# TheRealMainboardSCH.net
KiCad netlist of a schematic drawn in Altium Designer
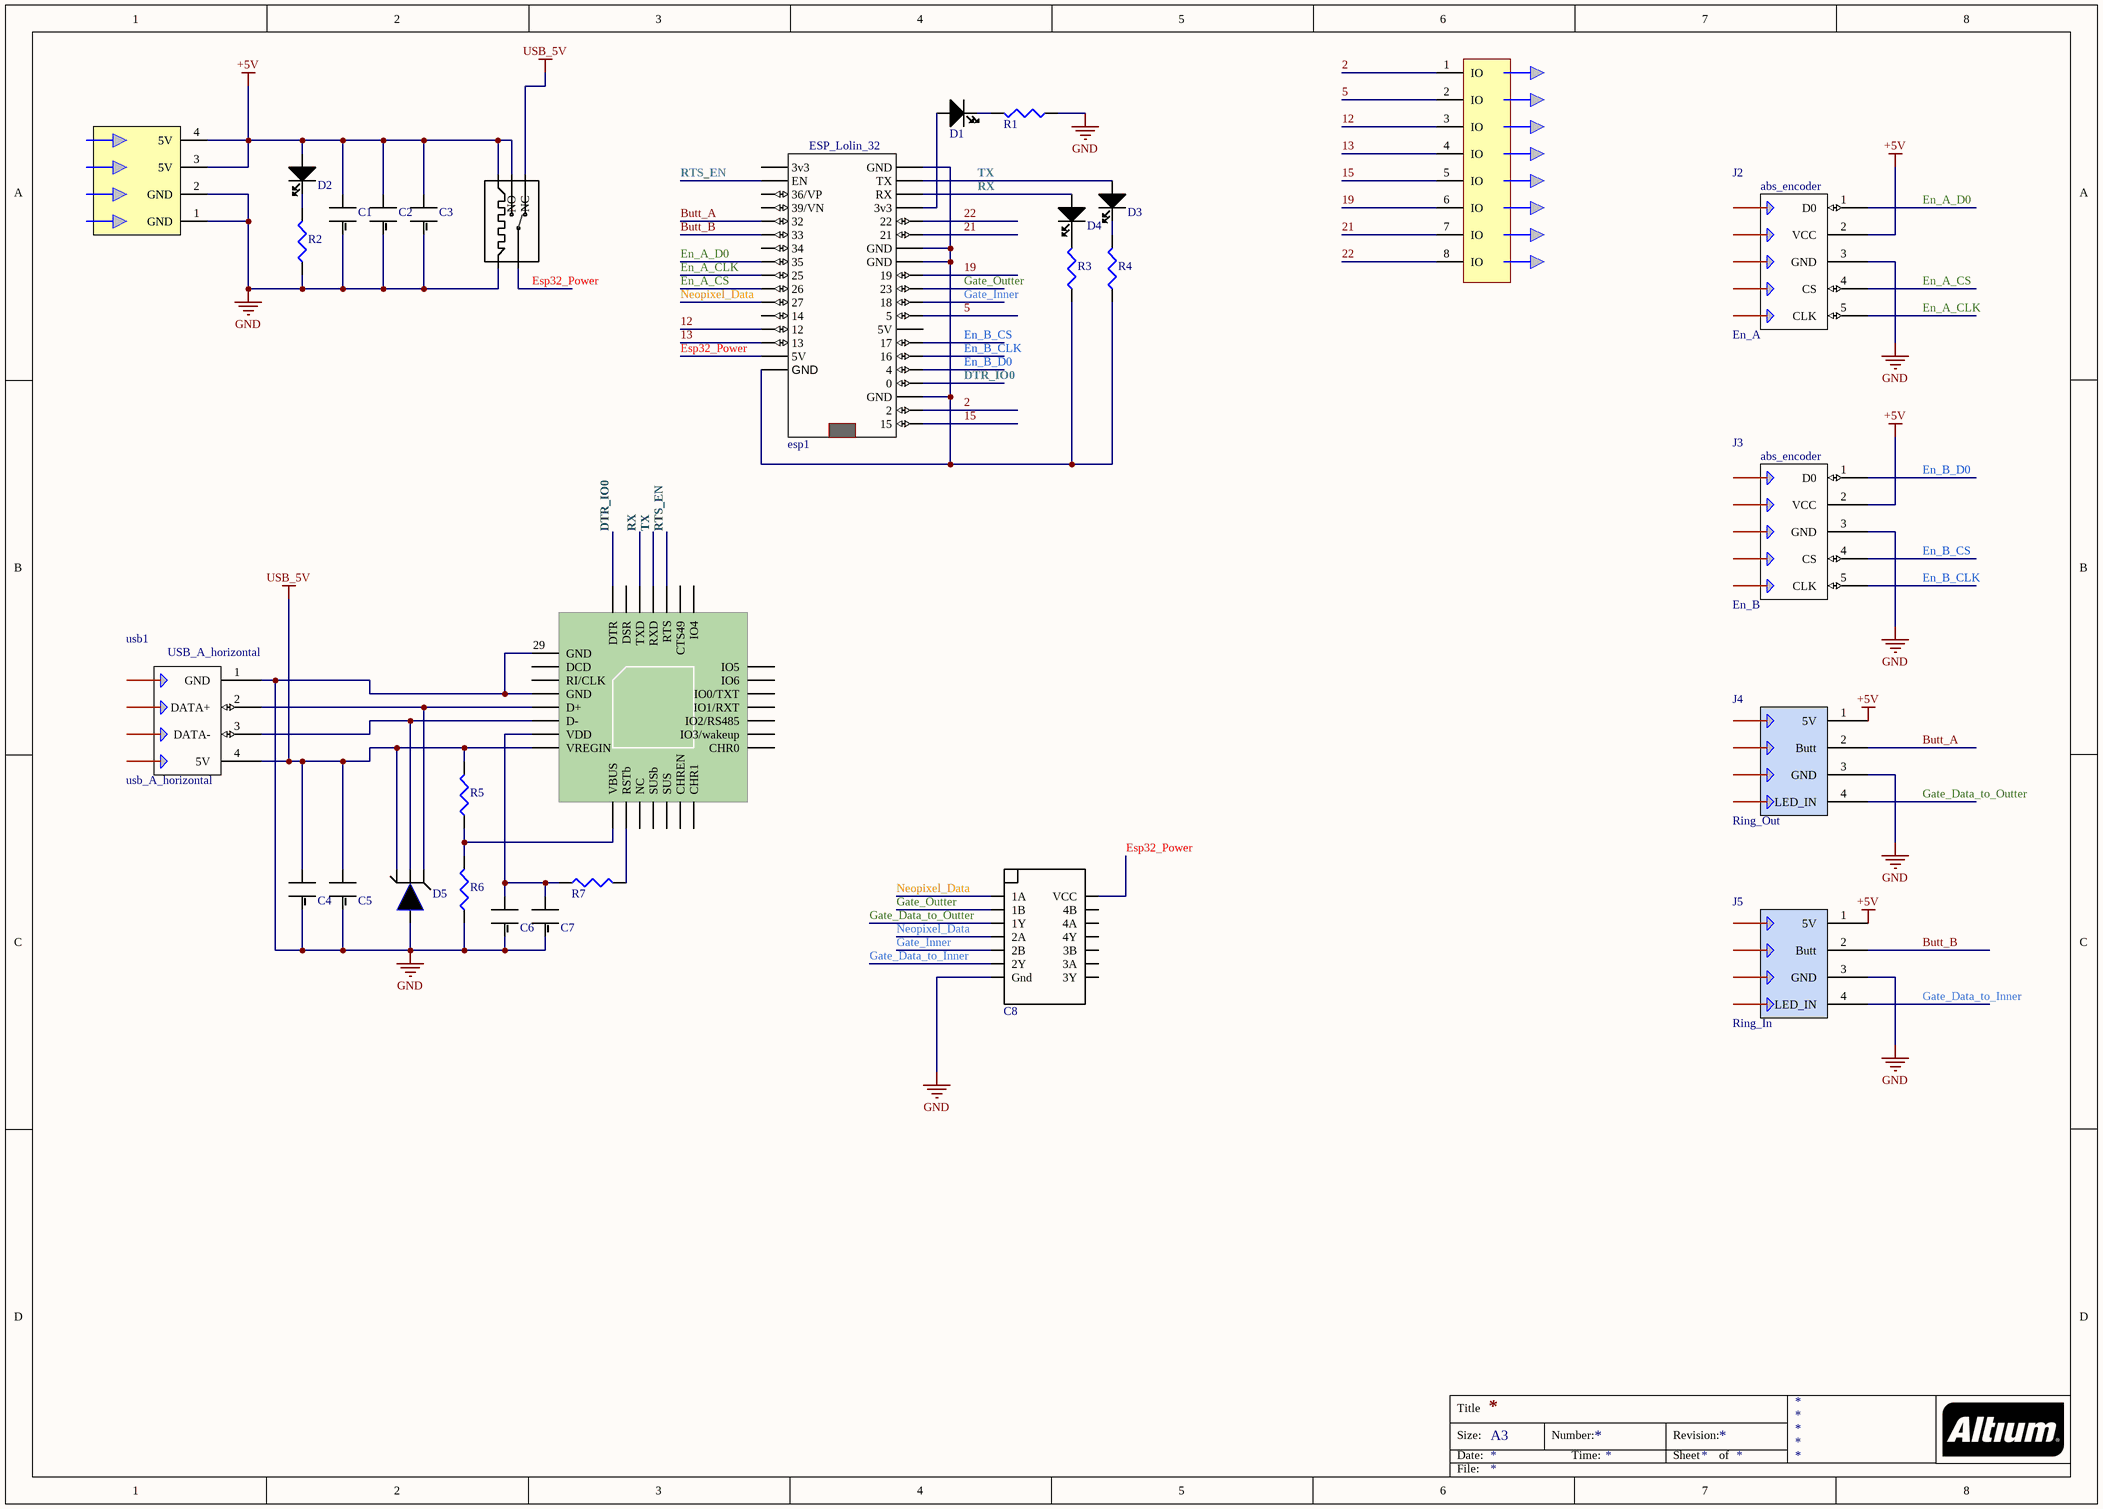
[diagram p0: TheRealMainboardSCH.SchDoc]

(export (version "E")
  (design (tool "Eeschema 10.0.6"))
  (components
    (comp (ref "C1")
      (value "EEU-FM0J331")
      (footprint "2.5mmCapacitor")
      (description "Cap 330 uF;  Tol 20%;  Vol-Rtg 6.3 VDC;  Radial;  6.3x11.2;  Bulk")
      (fields (field (name "TOLERANCE") "20%") (field (name "VOLTAGE") "6.3V"))
      (libsource (lib "WTFschlibra") (part "EEU-FM0J331"))
    )
    (comp (ref "C2")
      (value "EEU-FM0J331")
      (footprint "2.5mmCapacitor")
      (description "Cap 330 uF;  Tol 20%;  Vol-Rtg 6.3 VDC;  Radial;  6.3x11.2;  Bulk")
      (fields (field (name "TOLERANCE") "20%") (field (name "VOLTAGE") "6.3V"))
      (libsource (lib "WTFschlibra") (part "EEU-FM0J331"))
    )
    (comp (ref "C3")
      (value "EEU-FM0J331")
      (footprint "2.5mmCapacitor")
      (description "Cap 330 uF;  Tol 20%;  Vol-Rtg 6.3 VDC;  Radial;  6.3x11.2;  Bulk")
      (fields (field (name "TOLERANCE") "20%") (field (name "VOLTAGE") "6.3V"))
      (libsource (lib "WTFschlibra") (part "EEU-FM0J331"))
    )
    (comp (ref "C4")
      (value "C4R7")
      (footprint "Capacitor0603")
      (description "Cap Ceramic 4.7uF 6.3V X5R 20% Pad SMD 0402 85C T/R")
      (fields (field (name "TOLERANCE") "20%"))
      (libsource (lib "WTFschlibra") (part "capacitor0603"))
    )
    (comp (ref "C5")
      (value "C104")
      (footprint "Capacitor0603")
      (description "0.1uf")
      (fields (field (name "TOLERANCE") "20%"))
      (libsource (lib "WTFschlibra") (part "capacitor0603"))
    )
    (comp (ref "C6")
      (value "C104")
      (footprint "Capacitor0603")
      (description "4.7")
      (fields (field (name "TOLERANCE") "20%"))
      (libsource (lib "WTFschlibra") (part "capacitor0603"))
    )
    (comp (ref "C7")
      (value "C4R7")
      (footprint "Capacitor0603")
      (description "0.1")
      (fields (field (name "TOLERANCE") "20%"))
      (libsource (lib "WTFschlibra") (part "capacitor0603"))
    )
    (comp (ref "C8")
      (value "74hc08d")
      (footprint "SOP14(74hc08d)")
      (libsource (lib "WTFschlibra") (part "74HC08"))
    )
    (comp (ref "cp1")
      (value "CP2102N")
      (footprint "CP2102N_QFN28")
      (description "Full Speed USB to UART Bridge USB 2.0 3.3V T/R Automotive 28-Pin QFN EP")
      (libsource (lib "WTFschlibra") (part "CP2102N-A02-GQFN28R"))
    )
    (comp (ref "D1")
      (value "ESP")
      (footprint "LED0603")
      (description "LED BLUE CLEAR CHIP SMD")
      (libsource (lib "WTFschlibra") (part "LTST-C190TBKT"))
    )
    (comp (ref "D2")
      (value "P_on")
      (footprint "LED0603")
      (description "LED BLUE CLEAR CHIP SMD")
      (libsource (lib "WTFschlibra") (part "LTST-C190TBKT"))
    )
    (comp (ref "D3")
      (value "TXD")
      (footprint "LED0603")
      (description "LED BLUE CLEAR CHIP SMD")
      (libsource (lib "WTFschlibra") (part "LTST-C190TBKT"))
    )
    (comp (ref "D4")
      (value "RXD")
      (footprint "LED0603")
      (description "LED BLUE CLEAR CHIP SMD")
      (libsource (lib "WTFschlibra") (part "LTST-C190TBKT"))
    )
    (comp (ref "D5")
      (value "SP0503BAHTG")
      (footprint "SP0503BAHTG - SOT143-4")
      (description "ESD Suppressor TVS 5.5V 4-Pin(3+Tab) SOT-143 T/R")
      (libsource (lib "WTFschlibra") (part "SP0503BAHTG"))
    )
    (comp (ref "esp1")
      (value "processor")
      (footprint "ESP_32_socket")
      (libsource (lib "WTFschlibra") (part "ESP_32_lolin"))
    )
    (comp (ref "J1")
      (value "4.2mm 4pin 39300040")
      (footprint "4.2mm 4pos")
      (description "for neopixels array")
      (libsource (lib "WTFschlibra") (part "4.2mm 4pin 39300040"))
    )
    (comp (ref "J2")
      (value "En_A")
      (footprint "xh 2.54 5 pin")
      (libsource (lib "WTFschlibra") (part "Abs_encoder_pins"))
    )
    (comp (ref "J3")
      (value "En_B")
      (footprint "xh 2.54 5 pin")
      (libsource (lib "WTFschlibra") (part "Abs_encoder_pins"))
    )
    (comp (ref "J4")
      (value "Ring_Out")
      (footprint "XH 2.54 4 PIN")
      (libsource (lib "WTFschlibra") (part "To_rings_connector"))
    )
    (comp (ref "J5")
      (value "Ring_In")
      (footprint "XH 2.54 4 PIN")
      (libsource (lib "WTFschlibra") (part "To_rings_connector"))
    )
    (comp (ref "j6")
      (value "1x8 dupont io pins")
      (footprint "1x8 dupont")
      (libsource (lib "WTFschlibra") (part "1x8 dupont io pins"))
    )
    (comp (ref "R1")
      (value "360R")
      (footprint "R0805")
      (description "Res Thick Film 0805 360 Ohm 1% 0.125W(1/8W) ±100ppm/C Molded SMD Automotive Paper T/R")
      (fields (field (name "TOLERANCE") "1%"))
      (libsource (lib "WTFschlibra") (part "CRCW0805360RFKEA"))
    )
    (comp (ref "R2")
      (value "R360")
      (footprint "R0805")
      (description "Res Thick Film 0805 360 Ohm 1% 0.125W(1/8W) ±100ppm/C Molded SMD Automotive Paper T/R")
      (fields (field (name "TOLERANCE") "1%"))
      (libsource (lib "WTFschlibra") (part "CRCW0805360RFKEA"))
    )
    (comp (ref "R3")
      (value "R360")
      (footprint "R0805")
      (description "Res Thick Film 0805 360 Ohm 1% 0.125W(1/8W) ±100ppm/C Molded SMD Automotive Paper T/R")
      (fields (field (name "TOLERANCE") "1%"))
      (libsource (lib "WTFschlibra") (part "CRCW0805360RFKEA"))
    )
    (comp (ref "R4")
      (value "R360")
      (footprint "R0805")
      (description "Res Thick Film 0805 360 Ohm 1% 0.125W(1/8W) ±100ppm/C Molded SMD Automotive Paper T/R")
      (fields (field (name "TOLERANCE") "1%"))
      (libsource (lib "WTFschlibra") (part "CRCW0805360RFKEA"))
    )
    (comp (ref "R5")
      (value "R2212")
      (footprint "R0805")
      (description "Res Thick Film 0805 360 Ohm 1% 0.125W(1/8W) ±100ppm/C Molded SMD Automotive Paper T/R")
      (fields (field (name "TOLERANCE") "1%"))
      (libsource (lib "WTFschlibra") (part "resistor(CRCW0805360RFKEA"))
    )
    (comp (ref "R6")
      (value "R4752")
      (footprint "R0805")
      (description "Res Thick Film 0805 360 Ohm 1% 0.125W(1/8W) ±100ppm/C Molded SMD Automotive Paper T/R")
      (fields (field (name "TOLERANCE") "1%"))
      (libsource (lib "WTFschlibra") (part "resistor(CRCW0805360RFKEA"))
    )
    (comp (ref "R7")
      (value "R102")
      (footprint "R0805")
      (description "1Kohms")
      (fields (field (name "TOLERANCE") "1%"))
      (libsource (lib "WTFschlibra") (part "resistor(CRCW0805360RFKEA"))
    )
    (comp (ref "Relay1")
      (value "Omron_G5v_dc5")
      (footprint "G5v1_5vdc")
      (libsource (lib "WTFschlibra") (part "Omron_G5v_dc5"))
    )
    (comp (ref "usb1")
      (value "usb_A_horizontal")
      (footprint "HORIZONTAL_USB_A_MALE_SOCKET")
      (description "4 Position Single Port Socket Right Angle Type A Through Hole USB")
      (libsource (lib "WTFschlibra") (part "usb_A_horizontal"))
    )
  )
  (nets
    (net (code "1") (name "+5V") (class "Default")
      (node (ref "C1") (pin "2") (pinfunction "+_2") (pintype "passive"))
      (node (ref "C2") (pin "2") (pinfunction "+_2") (pintype "passive"))
      (node (ref "C3") (pin "2") (pinfunction "+_2") (pintype "passive"))
      (node (ref "D2") (pin "2") (pinfunction "2_2") (pintype "passive"))
      (node (ref "J1") (pin "3") (pinfunction "5V_3") (pintype "passive"))
      (node (ref "J1") (pin "4") (pinfunction "5V_4") (pintype "passive"))
      (node (ref "J2") (pin "2") (pinfunction "VCC_2") (pintype "power_in"))
      (node (ref "J3") (pin "2") (pinfunction "VCC_2") (pintype "power_in"))
      (node (ref "J4") (pin "1") (pinfunction "5V_1") (pintype "passive"))
      (node (ref "J5") (pin "1") (pinfunction "5V_1") (pintype "passive"))
      (node (ref "Relay1") (pin "1") (pinfunction "Coli_A_1") (pintype "passive"))
      (node (ref "Relay1") (pin "5") (pinfunction "NO_5") (pintype "passive"))
    )
    (net (code "2") (name "/2") (class "Default")
      (node (ref "esp1") (pin "19") (pinfunction "2_19") (pintype "bidirectional"))
      (node (ref "j6") (pin "1") (pinfunction "IO_1") (pintype "passive"))
    )
    (net (code "3") (name "/5") (class "Default")
      (node (ref "esp1") (pin "12") (pinfunction "5_12") (pintype "bidirectional"))
      (node (ref "j6") (pin "2") (pinfunction "IO_2") (pintype "passive"))
    )
    (net (code "4") (name "/12") (class "Default")
      (node (ref "esp1") (pin "33") (pinfunction "12_33") (pintype "bidirectional"))
      (node (ref "j6") (pin "3") (pinfunction "IO_3") (pintype "passive"))
    )
    (net (code "5") (name "/13") (class "Default")
      (node (ref "esp1") (pin "34") (pinfunction "13_34") (pintype "bidirectional"))
      (node (ref "j6") (pin "4") (pinfunction "IO_4") (pintype "passive"))
    )
    (net (code "6") (name "/15") (class "Default")
      (node (ref "esp1") (pin "20") (pinfunction "15_20") (pintype "bidirectional"))
      (node (ref "j6") (pin "5") (pinfunction "IO_5") (pintype "passive"))
    )
    (net (code "7") (name "/19") (class "Default")
      (node (ref "esp1") (pin "9") (pinfunction "19_9") (pintype "bidirectional"))
      (node (ref "j6") (pin "6") (pinfunction "IO_6") (pintype "passive"))
    )
    (net (code "8") (name "/21") (class "Default")
      (node (ref "esp1") (pin "6") (pinfunction "21_6") (pintype "bidirectional"))
      (node (ref "j6") (pin "7") (pinfunction "IO_7") (pintype "passive"))
    )
    (net (code "9") (name "/22") (class "Default")
      (node (ref "esp1") (pin "5") (pinfunction "22_5") (pintype "bidirectional"))
      (node (ref "j6") (pin "8") (pinfunction "IO_8") (pintype "passive"))
    )
    (net (code "10") (name "/Butt_A") (class "Default")
      (node (ref "J4") (pin "2") (pinfunction "Butt_2") (pintype "passive"))
      (node (ref "esp1") (pin "25") (pinfunction "32_25") (pintype "bidirectional"))
    )
    (net (code "11") (name "/Butt_B") (class "Default")
      (node (ref "J5") (pin "2") (pinfunction "Butt_2") (pintype "passive"))
      (node (ref "esp1") (pin "26") (pinfunction "33_26") (pintype "bidirectional"))
    )
    (net (code "12") (name "/DTR_IO0") (class "Default")
      (node (ref "cp1") (pin "28") (pinfunction "DTR_28") (pintype "passive"))
      (node (ref "esp1") (pin "17") (pinfunction "0_17") (pintype "bidirectional"))
    )
    (net (code "13") (name "/En_A_CLK") (class "Default")
      (node (ref "J2") (pin "5") (pinfunction "CLK_5") (pintype "bidirectional"))
      (node (ref "esp1") (pin "29") (pinfunction "25_29") (pintype "bidirectional"))
    )
    (net (code "14") (name "/En_A_CS") (class "Default")
      (node (ref "J2") (pin "4") (pinfunction "CS_4") (pintype "bidirectional"))
      (node (ref "esp1") (pin "30") (pinfunction "26_30") (pintype "bidirectional"))
    )
    (net (code "15") (name "/En_A_D0") (class "Default")
      (node (ref "J2") (pin "1") (pinfunction "D0_1") (pintype "bidirectional"))
      (node (ref "esp1") (pin "28") (pinfunction "35_28") (pintype "bidirectional"))
    )
    (net (code "16") (name "/En_B_CLK") (class "Default")
      (node (ref "J3") (pin "5") (pinfunction "CLK_5") (pintype "bidirectional"))
      (node (ref "esp1") (pin "15") (pinfunction "16_15") (pintype "bidirectional"))
    )
    (net (code "17") (name "/En_B_CS") (class "Default")
      (node (ref "J3") (pin "4") (pinfunction "CS_4") (pintype "bidirectional"))
      (node (ref "esp1") (pin "14") (pinfunction "17_14") (pintype "bidirectional"))
    )
    (net (code "18") (name "/En_B_D0") (class "Default")
      (node (ref "J3") (pin "1") (pinfunction "D0_1") (pintype "bidirectional"))
      (node (ref "esp1") (pin "16") (pinfunction "4_16") (pintype "bidirectional"))
    )
    (net (code "19") (name "/Esp32_Power") (class "Default")
      (node (ref "C8") (pin "14") (pinfunction "VCC_14") (pintype "passive"))
      (node (ref "Relay1") (pin "3") (pinfunction "COM_3") (pintype "passive"))
      (node (ref "esp1") (pin "35") (pinfunction "5V_35") (pintype "power_in"))
    )
    (net (code "20") (name "/Gate_Data_to_Inner") (class "Default")
      (node (ref "C8") (pin "6") (pinfunction "2Y_6") (pintype "passive"))
      (node (ref "J5") (pin "4") (pinfunction "LED_IN_4") (pintype "passive"))
    )
    (net (code "21") (name "/Gate_Data_to_Outter") (class "Default")
      (node (ref "C8") (pin "3") (pinfunction "1Y_3") (pintype "passive"))
      (node (ref "J4") (pin "4") (pinfunction "LED_IN_4") (pintype "passive"))
    )
    (net (code "22") (name "/Gate_Inner") (class "Default")
      (node (ref "C8") (pin "5") (pinfunction "2B_5") (pintype "passive"))
      (node (ref "esp1") (pin "11") (pinfunction "18_11") (pintype "bidirectional"))
    )
    (net (code "23") (name "/Gate_Outter") (class "Default")
      (node (ref "C8") (pin "2") (pinfunction "1B_2") (pintype "passive"))
      (node (ref "esp1") (pin "10") (pinfunction "23_10") (pintype "bidirectional"))
    )
    (net (code "24") (name "/Neopixel_Data") (class "Default")
      (node (ref "C8") (pin "1") (pinfunction "1A_1") (pintype "passive"))
      (node (ref "C8") (pin "4") (pinfunction "2A_4") (pintype "passive"))
      (node (ref "esp1") (pin "31") (pinfunction "27_31") (pintype "bidirectional"))
    )
    (net (code "25") (name "/RTS_EN") (class "Default")
      (node (ref "cp1") (pin "24") (pinfunction "RTS_24") (pintype "passive"))
      (node (ref "esp1") (pin "22") (pinfunction "EN_22") (pintype "passive"))
    )
    (net (code "26") (name "/RX") (class "Default")
      (node (ref "D4") (pin "2") (pinfunction "2_2") (pintype "passive"))
      (node (ref "cp1") (pin "26") (pinfunction "TXD_26") (pintype "passive"))
      (node (ref "esp1") (pin "3") (pinfunction "RX_3") (pintype "passive"))
    )
    (net (code "27") (name "/TX") (class "Default")
      (node (ref "D3") (pin "2") (pinfunction "2_2") (pintype "passive"))
      (node (ref "cp1") (pin "25") (pinfunction "RXD_25") (pintype "passive"))
      (node (ref "esp1") (pin "2") (pinfunction "TX_2") (pintype "passive"))
    )
    (net (code "28") (name "GND") (class "Default")
      (node (ref "C1") (pin "1") (pinfunction "-_1") (pintype "passive"))
      (node (ref "C2") (pin "1") (pinfunction "-_1") (pintype "passive"))
      (node (ref "C3") (pin "1") (pinfunction "-_1") (pintype "passive"))
      (node (ref "C4") (pin "1") (pinfunction "-_1") (pintype "passive"))
      (node (ref "C5") (pin "1") (pinfunction "-_1") (pintype "passive"))
      (node (ref "C6") (pin "1") (pinfunction "-_1") (pintype "passive"))
      (node (ref "C7") (pin "1") (pinfunction "-_1") (pintype "passive"))
      (node (ref "C8") (pin "7") (pinfunction "Gnd_7") (pintype "passive"))
      (node (ref "D5") (pin "1") (pinfunction "+_1") (pintype "passive"))
      (node (ref "J1") (pin "1") (pinfunction "GND_1") (pintype "passive"))
      (node (ref "J1") (pin "2") (pinfunction "GND_2") (pintype "passive"))
      (node (ref "J2") (pin "3") (pinfunction "GND_3") (pintype "power_in"))
      (node (ref "J3") (pin "3") (pinfunction "GND_3") (pintype "power_in"))
      (node (ref "J4") (pin "3") (pinfunction "GND_3") (pintype "passive"))
      (node (ref "J5") (pin "3") (pinfunction "GND_3") (pintype "passive"))
      (node (ref "R1") (pin "1") (pinfunction "1_1") (pintype "passive"))
      (node (ref "R2") (pin "1") (pinfunction "1_1") (pintype "passive"))
      (node (ref "R6") (pin "1") (pinfunction "1_1") (pintype "passive"))
      (node (ref "Relay1") (pin "2") (pinfunction "Coli_B_2") (pintype "passive"))
      (node (ref "cp1") (pin "29") (pinfunction "GND_29") (pintype "passive"))
      (node (ref "cp1") (pin "3") (pinfunction "GND_3") (pintype "passive"))
      (node (ref "usb1") (pin "1") (pinfunction "GND_1") (pintype "power_in"))
    )
    (net (code "29") (name "Net-(C6-+)") (class "Default")
      (node (ref "C6") (pin "2") (pinfunction "+_2") (pintype "passive"))
      (node (ref "C7") (pin "2") (pinfunction "+_2") (pintype "passive"))
      (node (ref "R7") (pin "1") (pinfunction "1_1") (pintype "passive"))
      (node (ref "cp1") (pin "6") (pinfunction "VDD_6") (pintype "passive"))
    )
    (net (code "30") (name "Net-(D1-Pad1)") (class "Default")
      (node (ref "D1") (pin "1") (pinfunction "1_1") (pintype "passive"))
      (node (ref "R1") (pin "2") (pinfunction "2_2") (pintype "passive"))
    )
    (net (code "31") (name "Net-(D1-Pad2)") (class "Default")
      (node (ref "D1") (pin "2") (pinfunction "2_2") (pintype "passive"))
      (node (ref "esp1") (pin "4") (pinfunction "3v3_4") (pintype "power_in"))
    )
    (net (code "32") (name "Net-(D2-Pad1)") (class "Default")
      (node (ref "D2") (pin "1") (pinfunction "1_1") (pintype "passive"))
      (node (ref "R2") (pin "2") (pinfunction "2_2") (pintype "passive"))
    )
    (net (code "33") (name "Net-(D3-Pad1)") (class "Default")
      (node (ref "D3") (pin "1") (pinfunction "1_1") (pintype "passive"))
      (node (ref "R4") (pin "2") (pinfunction "2_2") (pintype "passive"))
    )
    (net (code "34") (name "Net-(D4-Pad1)") (class "Default")
      (node (ref "D4") (pin "1") (pinfunction "1_1") (pintype "passive"))
      (node (ref "R3") (pin "2") (pinfunction "2_2") (pintype "passive"))
    )
    (net (code "35") (name "Net-(R3-Pad1)") (class "Default")
      (node (ref "R3") (pin "1") (pinfunction "1_1") (pintype "passive"))
      (node (ref "R4") (pin "1") (pinfunction "1_1") (pintype "passive"))
      (node (ref "esp1") (pin "1") (pinfunction "GND_1") (pintype "power_in"))
      (node (ref "esp1") (pin "18") (pinfunction "GND_18") (pintype "power_in"))
      (node (ref "esp1") (pin "36") (pinfunction "GND_36") (pintype "power_in"))
      (node (ref "esp1") (pin "7") (pinfunction "GND_7") (pintype "power_in"))
      (node (ref "esp1") (pin "8") (pinfunction "GND_8") (pintype "power_in"))
    )
    (net (code "36") (name "Net-(cp1-D+)") (class "Default")
      (node (ref "D5") (pin "2") (pinfunction "2_2") (pintype "passive"))
      (node (ref "cp1") (pin "4") (pinfunction "D+_4") (pintype "passive"))
      (node (ref "usb1") (pin "2") (pinfunction "DATA+_2") (pintype "bidirectional"))
    )
    (net (code "37") (name "Net-(cp1-D-)") (class "Default")
      (node (ref "D5") (pin "3") (pinfunction "3_3") (pintype "passive"))
      (node (ref "cp1") (pin "5") (pinfunction "D-_5") (pintype "passive"))
      (node (ref "usb1") (pin "3") (pinfunction "DATA-_3") (pintype "bidirectional"))
    )
    (net (code "38") (name "Net-(cp1-RSTb)") (class "Default")
      (node (ref "R7") (pin "2") (pinfunction "2_2") (pintype "passive"))
      (node (ref "cp1") (pin "9") (pinfunction "RSTb_9") (pintype "passive"))
    )
    (net (code "39") (name "Net-(cp1-VBUS)") (class "Default")
      (node (ref "R5") (pin "1") (pinfunction "1_1") (pintype "passive"))
      (node (ref "R6") (pin "2") (pinfunction "2_2") (pintype "passive"))
      (node (ref "cp1") (pin "8") (pinfunction "VBUS_8") (pintype "passive"))
    )
    (net (code "40") (name "USB_5V") (class "Default")
      (node (ref "C4") (pin "2") (pinfunction "+_2") (pintype "passive"))
      (node (ref "C5") (pin "2") (pinfunction "+_2") (pintype "passive"))
      (node (ref "D5") (pin "4") (pinfunction "4_4") (pintype "passive"))
      (node (ref "R5") (pin "2") (pinfunction "2_2") (pintype "passive"))
      (node (ref "Relay1") (pin "4") (pinfunction "NC_4") (pintype "passive"))
      (node (ref "cp1") (pin "7") (pinfunction "VREGIN_7") (pintype "passive"))
      (node (ref "usb1") (pin "4") (pinfunction "5V_4") (pintype "power_in"))
    )
    (net (code "41") (name "unconnected-(C8-3A-Pad9)") (class "Default")
      (node (ref "C8") (pin "9") (pinfunction "3A_9") (pintype "passive"))
    )
    (net (code "42") (name "unconnected-(C8-3B-Pad10)") (class "Default")
      (node (ref "C8") (pin "10") (pinfunction "3B_10") (pintype "passive"))
    )
    (net (code "43") (name "unconnected-(C8-3Y-Pad8)") (class "Default")
      (node (ref "C8") (pin "8") (pinfunction "3Y_8") (pintype "passive"))
    )
    (net (code "44") (name "unconnected-(C8-4A-Pad12)") (class "Default")
      (node (ref "C8") (pin "12") (pinfunction "4A_12") (pintype "passive"))
    )
    (net (code "45") (name "unconnected-(C8-4B-Pad13)") (class "Default")
      (node (ref "C8") (pin "13") (pinfunction "4B_13") (pintype "passive"))
    )
    (net (code "46") (name "unconnected-(C8-4Y-Pad11)") (class "Default")
      (node (ref "C8") (pin "11") (pinfunction "4Y_11") (pintype "passive"))
    )
    (net (code "47") (name "unconnected-(cp1-CHR0-Pad15)") (class "Default")
      (node (ref "cp1") (pin "15") (pinfunction "CHR0_15") (pintype "passive"))
    )
    (net (code "48") (name "unconnected-(cp1-CHR1-Pad14)") (class "Default")
      (node (ref "cp1") (pin "14") (pinfunction "CHR1_14") (pintype "passive"))
    )
    (net (code "49") (name "unconnected-(cp1-CHREN-Pad13)") (class "Default")
      (node (ref "cp1") (pin "13") (pinfunction "CHREN_13") (pintype "passive"))
    )
    (net (code "50") (name "unconnected-(cp1-CTS49-Pad23)") (class "Default")
      (node (ref "cp1") (pin "23") (pinfunction "CTS49_23") (pintype "passive"))
    )
    (net (code "51") (name "unconnected-(cp1-DCD-Pad1)") (class "Default")
      (node (ref "cp1") (pin "1") (pinfunction "DCD_1") (pintype "passive"))
    )
    (net (code "52") (name "unconnected-(cp1-DSR-Pad27)") (class "Default")
      (node (ref "cp1") (pin "27") (pinfunction "DSR_27") (pintype "passive"))
    )
    (net (code "53") (name "unconnected-(cp1-IO0{slash}TXT-Pad19)") (class "Default")
      (node (ref "cp1") (pin "19") (pinfunction "IO0/TXT_19") (pintype "passive"))
    )
    (net (code "54") (name "unconnected-(cp1-IO1{slash}RXT-Pad18)") (class "Default")
      (node (ref "cp1") (pin "18") (pinfunction "IO1/RXT_18") (pintype "passive"))
    )
    (net (code "55") (name "unconnected-(cp1-IO2{slash}RS485-Pad17)") (class "Default")
      (node (ref "cp1") (pin "17") (pinfunction "IO2/RS485_17") (pintype "passive"))
    )
    (net (code "56") (name "unconnected-(cp1-IO3{slash}wakeup-Pad16)") (class "Default")
      (node (ref "cp1") (pin "16") (pinfunction "IO3/wakeup_16") (pintype "passive"))
    )
    (net (code "57") (name "unconnected-(cp1-IO4-Pad22)") (class "Default")
      (node (ref "cp1") (pin "22") (pinfunction "IO4_22") (pintype "passive"))
    )
    (net (code "58") (name "unconnected-(cp1-IO5-Pad21)") (class "Default")
      (node (ref "cp1") (pin "21") (pinfunction "IO5_21") (pintype "passive"))
    )
    (net (code "59") (name "unconnected-(cp1-IO6-Pad20)") (class "Default")
      (node (ref "cp1") (pin "20") (pinfunction "IO6_20") (pintype "passive"))
    )
    (net (code "60") (name "unconnected-(cp1-NC-Pad10)") (class "Default")
      (node (ref "cp1") (pin "10") (pinfunction "NC_10") (pintype "passive"))
    )
    (net (code "61") (name "unconnected-(cp1-RI{slash}CLK-Pad2)") (class "Default")
      (node (ref "cp1") (pin "2") (pinfunction "RI/CLK_2") (pintype "passive"))
    )
    (net (code "62") (name "unconnected-(cp1-SUS-Pad12)") (class "Default")
      (node (ref "cp1") (pin "12") (pinfunction "SUS_12") (pintype "passive"))
    )
    (net (code "63") (name "unconnected-(cp1-SUSb-Pad11)") (class "Default")
      (node (ref "cp1") (pin "11") (pinfunction "SUSb_11") (pintype "passive"))
    )
    (net (code "64") (name "unconnected-(esp1-3v3-Pad21)") (class "Default")
      (node (ref "esp1") (pin "21") (pinfunction "3v3_21") (pintype "power_in"))
    )
    (net (code "65") (name "unconnected-(esp1-5V-Pad13)") (class "Default")
      (node (ref "esp1") (pin "13") (pinfunction "5V_13") (pintype "power_in"))
    )
    (net (code "66") (name "unconnected-(esp1-14-Pad32)") (class "Default")
      (node (ref "esp1") (pin "32") (pinfunction "14_32") (pintype "bidirectional"))
    )
    (net (code "67") (name "unconnected-(esp1-34-Pad27)") (class "Default")
      (node (ref "esp1") (pin "27") (pinfunction "34_27") (pintype "bidirectional"))
    )
    (net (code "68") (name "unconnected-(esp1-36{slash}VP-Pad23)") (class "Default")
      (node (ref "esp1") (pin "23") (pinfunction "36/VP_23") (pintype "bidirectional"))
    )
    (net (code "69") (name "unconnected-(esp1-39{slash}VN-Pad24)") (class "Default")
      (node (ref "esp1") (pin "24") (pinfunction "39/VN_24") (pintype "bidirectional"))
    )
  )
)
